# USBCOMPORT-TTL.net
KiCad netlist of a schematic drawn in Altium Designer
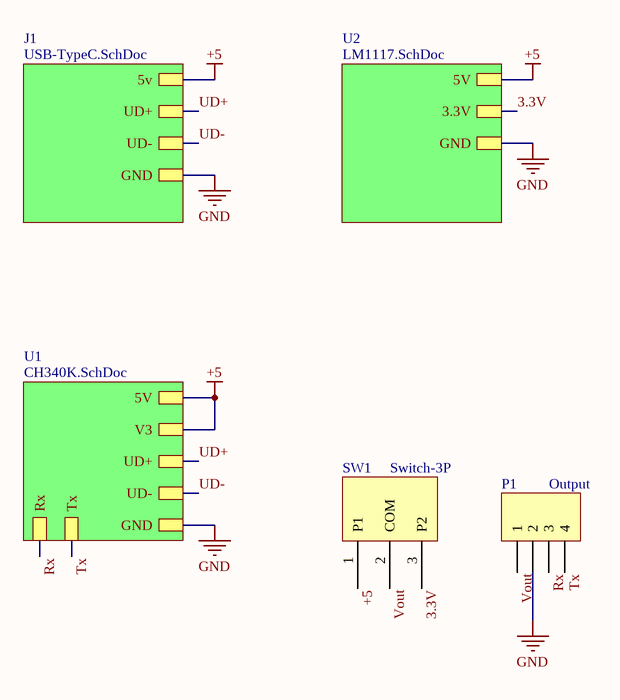
[diagram p0: USBCOMPORT-TTL.SchDoc]

(export (version "E")
  (design (tool "Eeschema 10.0.6"))
  (components
    (comp (ref "P1")
      (value "Output")
      (footprint "HDR1X4")
      (description "Header, 4-Pin")
      (fields (field (name "PUBLISHER") "Altium Limited"))
      (libsource (lib "Miscellaneous Connectors") (part "Header 4"))
    )
    (comp (ref "SW1")
      (value "Switch-3P")
      (footprint "SS-12D00(1P2T)")
      (libsource (lib "Components_myself") (part "Switch-3P"))
    )
  )
  (nets
    (net (code "1") (name "+5") (class "Default")
      (node (ref "SW1") (pin "1") (pinfunction "P1_1") (pintype "passive"))
    )
    (net (code "2") (name "/3.3V") (class "Default")
      (node (ref "SW1") (pin "3") (pinfunction "P2_3") (pintype "passive"))
    )
    (net (code "3") (name "/Rx") (class "Default")
      (node (ref "P1") (pin "3") (pinfunction "3_3") (pintype "passive"))
    )
    (net (code "4") (name "/Tx") (class "Default")
      (node (ref "P1") (pin "4") (pinfunction "4_4") (pintype "passive"))
    )
    (net (code "7") (name "/Vout") (class "Default")
      (node (ref "P1") (pin "1") (pinfunction "1_1") (pintype "passive"))
      (node (ref "SW1") (pin "2") (pinfunction "COM_2") (pintype "passive"))
    )
    (net (code "8") (name "GND") (class "Default")
      (node (ref "P1") (pin "2") (pinfunction "2_2") (pintype "passive"))
    )
  )
)
